# MCU_IO.net
KiCad netlist of a schematic drawn in Altium Designer
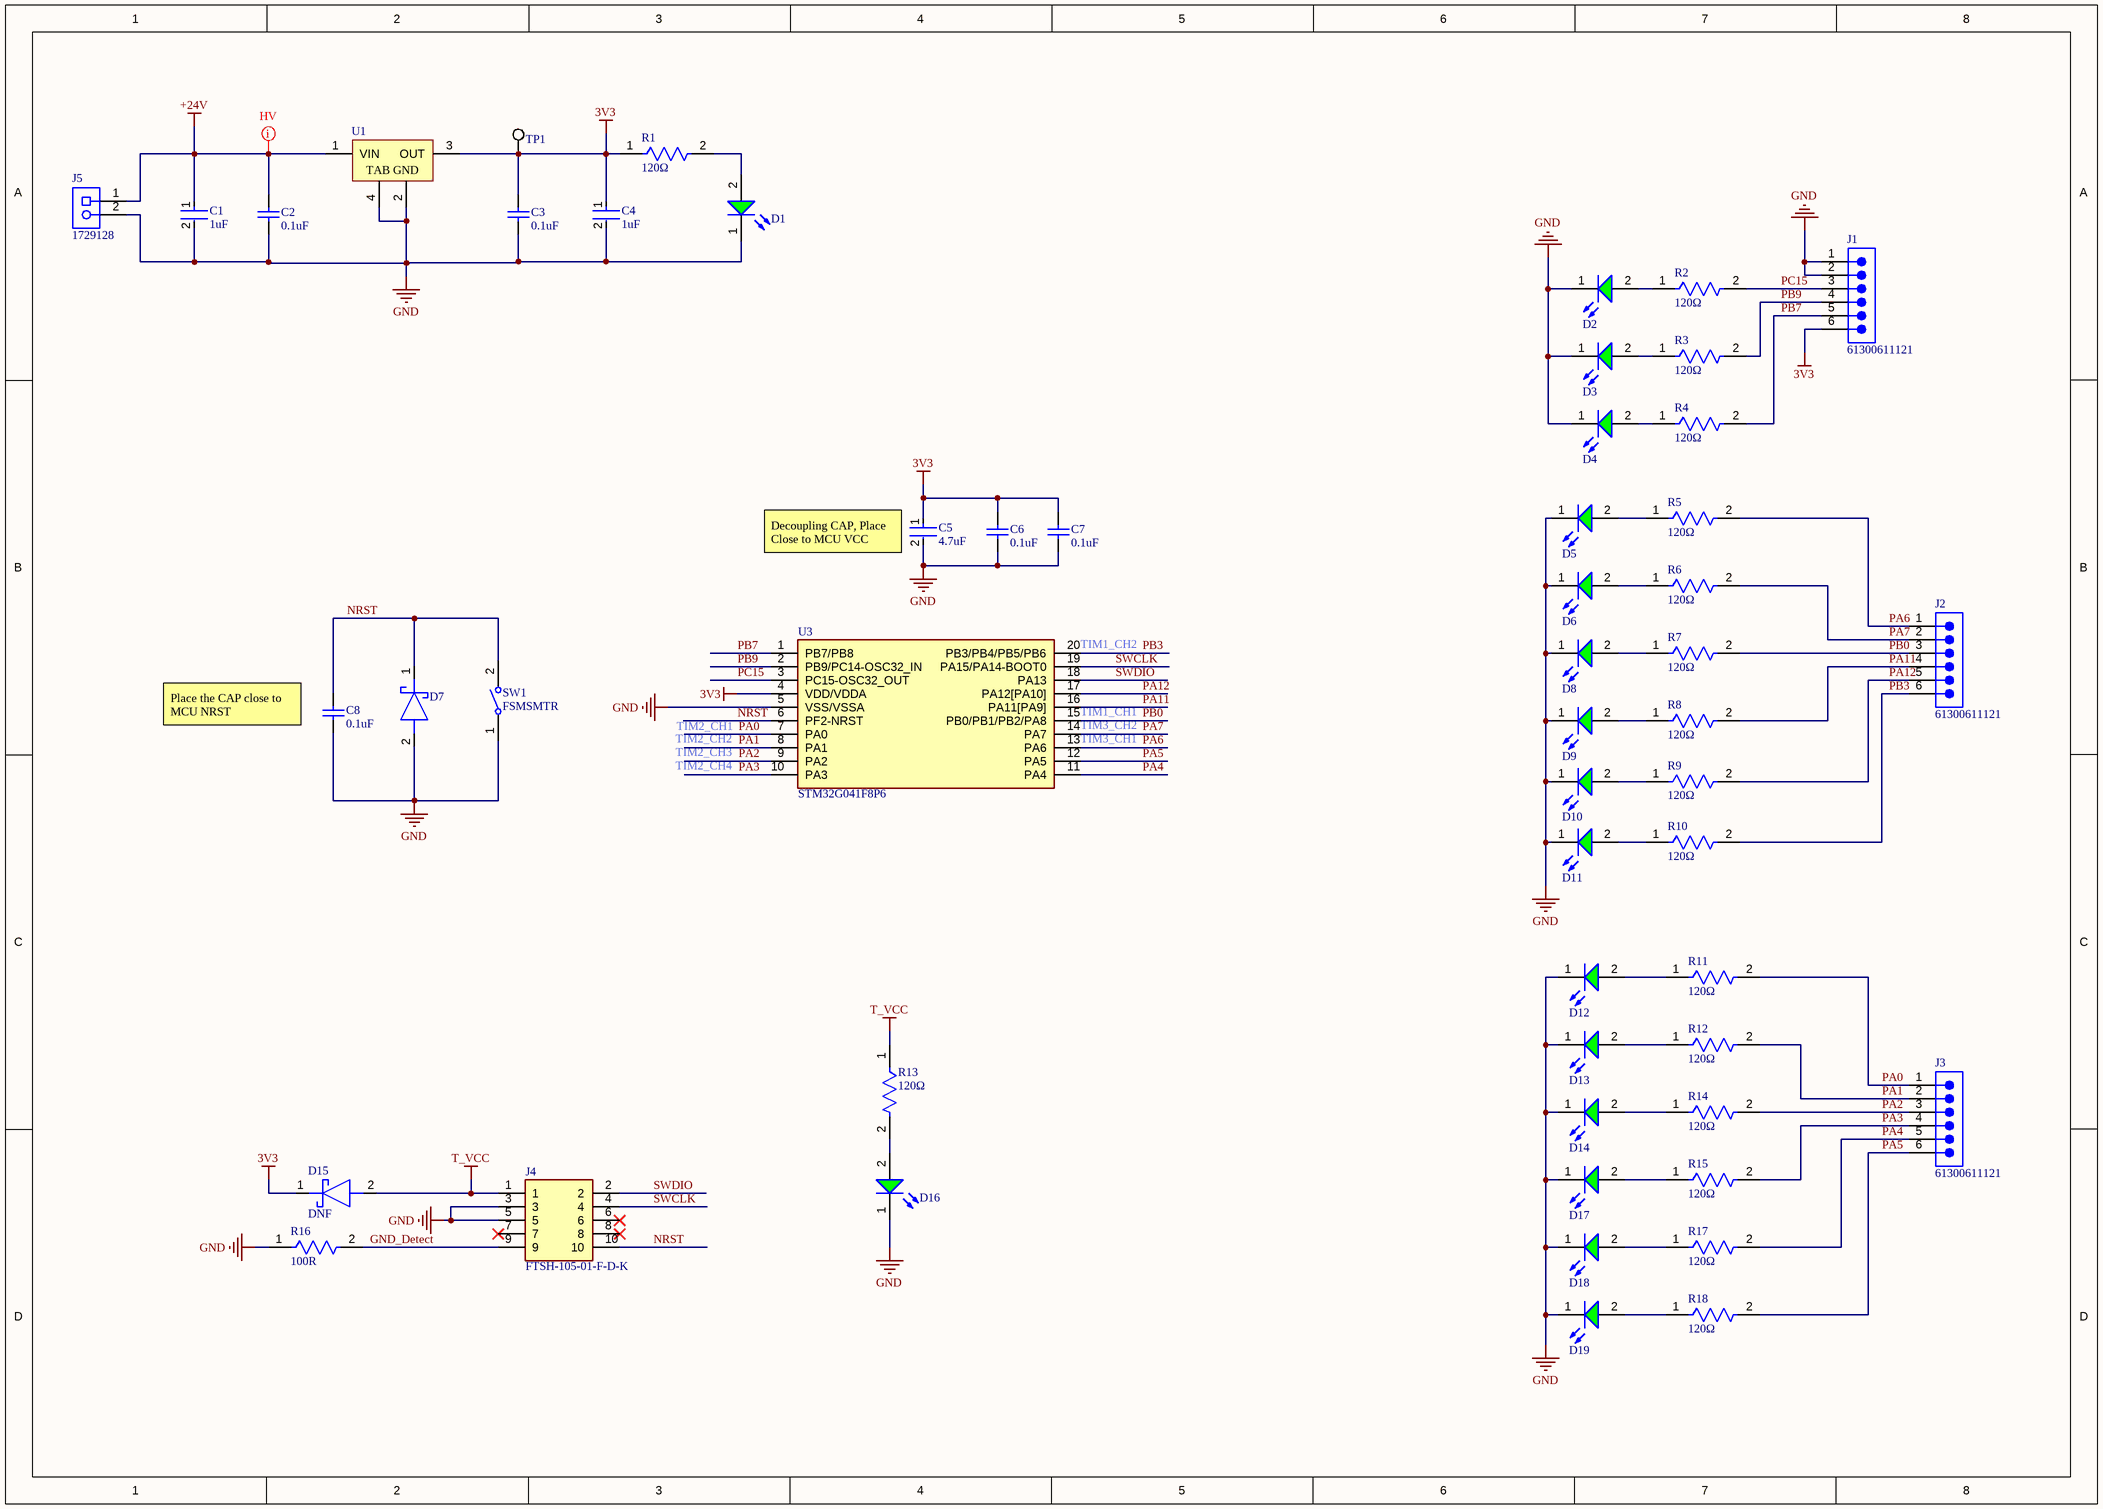
[diagram p0: MCU_IO.SchDoc]

(export (version "E")
  (design (tool "Eeschema 10.0.6"))
  (components
    (comp (ref "C1")
      (value "CC0805JKX7R9BB105")
      (footprint "FP-CC0805-0_2-1_45-MFG")
      (description "CAP CER 1UF 50V X7R 0805")
      (fields (field (name "CAPACITANCE") "1uF") (field (name "TOLERANCE") "5%"))
      (libsource (lib "Altium Content Vault") (part "02cd4be3c70576c341d710602a673aa"))
    )
    (comp (ref "C2")
      (value "0.1uF")
      (footprint "CAPC2013X94X50ML25T25")
      (description "CAP CER 0.1UF 100V X7R 0805")
      (fields
        (field (name "PART NUMBER") "LD051C104KAB2A")
        (field (name "MANUFACTURER") "AVX Interconnect / Elco")
      )
      (libsource (lib "Altium Content Vault") (part "CAP"))
    )
    (comp (ref "C3")
      (value "0.1uF")
      (footprint "CAPC2013X94X50ML25T25")
      (description "CAP CER 0.1UF 100V X7R 0805")
      (fields
        (field (name "PART NUMBER") "LD051C104KAB2A")
        (field (name "MANUFACTURER") "AVX Interconnect / Elco")
      )
      (libsource (lib "Altium Content Vault") (part "CAP"))
    )
    (comp (ref "C4")
      (value "CC0805JKX7R9BB105")
      (footprint "FP-CC0805-0_2-1_45-MFG")
      (description "CAP CER 1UF 50V X7R 0805")
      (fields (field (name "CAPACITANCE") "1uF") (field (name "TOLERANCE") "5%"))
      (libsource (lib "Altium Content Vault") (part "02cd4be3c70576c341d710602a673aa"))
    )
    (comp (ref "C5")
      (value "CGA4J3X7R1C475M125AE")
      (footprint "FP-CGA4J-IPC_B")
      (description "Cap Ceramic 4.7uF 16V X7R 20% Pad SMD 0805 +125°C Automotive T/R")
      (fields (field (name "TOLERANCE") "20%") (field (name "CAPACITANCE") "4.7uF"))
      (libsource (lib "Altium Content Vault") (part "b4654b650e69147ec39a6b967a45e02"))
    )
    (comp (ref "C6")
      (value "0.1uF")
      (footprint "CAPC2013X94X50ML25T25")
      (description "CAP CER 0.1UF 100V X7R 0805")
      (fields
        (field (name "PART NUMBER") "LD051C104KAB2A")
        (field (name "MANUFACTURER") "AVX Interconnect / Elco")
      )
      (libsource (lib "Altium Content Vault") (part "CAP"))
    )
    (comp (ref "C7")
      (value "0.1uF")
      (footprint "CAPC2013X94X50ML25T25")
      (description "CAP CER 0.1UF 100V X7R 0805")
      (fields
        (field (name "PART NUMBER") "LD051C104KAB2A")
        (field (name "MANUFACTURER") "AVX Interconnect / Elco")
      )
      (libsource (lib "Altium Content Vault") (part "CAP"))
    )
    (comp (ref "C8")
      (value "0.1uF")
      (footprint "CAPC2013X94X50ML25T25")
      (description "CAP CER 0.1UF 100V X7R 0805")
      (fields
        (field (name "PART NUMBER") "LD051C104KAB2A")
        (field (name "MANUFACTURER") "AVX Interconnect / Elco")
      )
      (libsource (lib "Altium Content Vault") (part "CAP"))
    )
    (comp (ref "D1")
      (value "150080GS75000")
      (footprint "WL-SMCW_0805_150080xx75000")
      (libsource (lib "Altium Content Vault") (part "LED_Green_2A-1K"))
    )
    (comp (ref "D2")
      (value "150080GS75000")
      (footprint "WL-SMCW_0805_150080xx75000")
      (libsource (lib "Altium Content Vault") (part "LED_Green_2A-1K"))
    )
    (comp (ref "D3")
      (value "150080GS75000")
      (footprint "WL-SMCW_0805_150080xx75000")
      (libsource (lib "Altium Content Vault") (part "LED_Green_2A-1K"))
    )
    (comp (ref "D4")
      (value "150080GS75000")
      (footprint "WL-SMCW_0805_150080xx75000")
      (libsource (lib "Altium Content Vault") (part "LED_Green_2A-1K"))
    )
    (comp (ref "D5")
      (value "150080GS75000")
      (footprint "WL-SMCW_0805_150080xx75000")
      (libsource (lib "Altium Content Vault") (part "LED_Green_2A-1K"))
    )
    (comp (ref "D6")
      (value "150080GS75000")
      (footprint "WL-SMCW_0805_150080xx75000")
      (libsource (lib "Altium Content Vault") (part "LED_Green_2A-1K"))
    )
    (comp (ref "D7")
      (value "SD0805S020S1R0")
      (footprint "SamacSys:SD0805S020S1R0")
      (description "Schottky Diode")
      (fields (field (name "MOUSER PART NUMBER") "581-SD0805S020S1R0"))
      (libsource (lib "*") (part "SD0805S020S1R0"))
    )
    (comp (ref "D8")
      (value "150080GS75000")
      (footprint "WL-SMCW_0805_150080xx75000")
      (libsource (lib "Altium Content Vault") (part "LED_Green_2A-1K"))
    )
    (comp (ref "D9")
      (value "150080GS75000")
      (footprint "WL-SMCW_0805_150080xx75000")
      (libsource (lib "Altium Content Vault") (part "LED_Green_2A-1K"))
    )
    (comp (ref "D10")
      (value "150080GS75000")
      (footprint "WL-SMCW_0805_150080xx75000")
      (libsource (lib "Altium Content Vault") (part "LED_Green_2A-1K"))
    )
    (comp (ref "D11")
      (value "150080GS75000")
      (footprint "WL-SMCW_0805_150080xx75000")
      (libsource (lib "Altium Content Vault") (part "LED_Green_2A-1K"))
    )
    (comp (ref "D12")
      (value "150080GS75000")
      (footprint "WL-SMCW_0805_150080xx75000")
      (libsource (lib "Altium Content Vault") (part "LED_Green_2A-1K"))
    )
    (comp (ref "D13")
      (value "150080GS75000")
      (footprint "WL-SMCW_0805_150080xx75000")
      (libsource (lib "Altium Content Vault") (part "LED_Green_2A-1K"))
    )
    (comp (ref "D14")
      (value "150080GS75000")
      (footprint "WL-SMCW_0805_150080xx75000")
      (libsource (lib "Altium Content Vault") (part "LED_Green_2A-1K"))
    )
    (comp (ref "D15")
      (value "DNF")
      (footprint "SamacSys:SD0805S020S1R0")
      (description "Schottky Diode")
      (fields
        (field (name "MANUFACTURER_PART_NUMBER") "SD0805S020S1R0")
        (field (name "MOUSER PART NUMBER") "581-SD0805S020S1R0")
      )
      (libsource (lib "*") (part "SD0805S020S1R0"))
    )
    (comp (ref "D16")
      (value "150080GS75000")
      (footprint "WL-SMCW_0805_150080xx75000")
      (libsource (lib "Altium Content Vault") (part "LED_Green_2A-1K"))
    )
    (comp (ref "D17")
      (value "150080GS75000")
      (footprint "WL-SMCW_0805_150080xx75000")
      (libsource (lib "Altium Content Vault") (part "LED_Green_2A-1K"))
    )
    (comp (ref "D18")
      (value "150080GS75000")
      (footprint "WL-SMCW_0805_150080xx75000")
      (libsource (lib "Altium Content Vault") (part "LED_Green_2A-1K"))
    )
    (comp (ref "D19")
      (value "150080GS75000")
      (footprint "WL-SMCW_0805_150080xx75000")
      (libsource (lib "Altium Content Vault") (part "LED_Green_2A-1K"))
    )
    (comp (ref "J1")
      (value "61300611121")
      (footprint "61300611121")
      (libsource (lib "Altium Content Vault") (part "Header_Male_1R_06P"))
    )
    (comp (ref "J2")
      (value "61300611121")
      (footprint "61300611121")
      (libsource (lib "Altium Content Vault") (part "Header_Male_1R_06P"))
    )
    (comp (ref "J3")
      (value "61300611121")
      (footprint "61300611121")
      (libsource (lib "Altium Content Vault") (part "Header_Male_1R_06P"))
    )
    (comp (ref "J4")
      (value "FTSH-105-01-F-D-K")
      (footprint "SamacSys:FTSH-105-XX-YYY-D-K")
      (description "Connector")
      (fields (field (name "MOUSER PART NUMBER") "200-FTSH10501FDK"))
      (libsource (lib "*") (part "FTSH-105-01-F-D-K"))
    )
    (comp (ref "J5")
      (value "1729128")
      (footprint "PHOE-1729128-2_V")
      (description "PCB Terminal Block, 13.5 A, 400 V, 2-Pin THD, RoHS, Bulk")
      (fields (field (name "MANUFACTURER") "Phoenix Contact"))
      (libsource (lib "Altium Content Vault") (part "CN-2P-F-R2"))
    )
    (comp (ref "R1")
      (value "CRGP0805F120R")
      (footprint "FP-CRGP0805-IPC_C")
      (description "CRGP0805 120Ω 0.33W ±100ppm/°C 1% 150V")
      (fields
        (field (name "RESISTANCE") "120Ω")
        (field (name "OCTOPART") "https://octopart.com/crgp0805f120r-te+connectivity-91018785")
        (field (name "MANUFACTURER") "TE")
      )
      (libsource (lib "Altium Content Vault") (part "1029c3af85768c4190bb7ad29bc67b5"))
    )
    (comp (ref "R2")
      (value "CRGP0805F120R")
      (footprint "FP-CRGP0805-IPC_C")
      (description "CRGP0805 120Ω 0.33W ±100ppm/°C 1% 150V")
      (fields
        (field (name "RESISTANCE") "120Ω")
        (field (name "OCTOPART") "https://octopart.com/crgp0805f120r-te+connectivity-91018785")
        (field (name "MANUFACTURER") "TE")
      )
      (libsource (lib "Altium Content Vault") (part "1029c3af85768c4190bb7ad29bc67b5"))
    )
    (comp (ref "R3")
      (value "CRGP0805F120R")
      (footprint "FP-CRGP0805-IPC_C")
      (description "CRGP0805 120Ω 0.33W ±100ppm/°C 1% 150V")
      (fields
        (field (name "RESISTANCE") "120Ω")
        (field (name "OCTOPART") "https://octopart.com/crgp0805f120r-te+connectivity-91018785")
        (field (name "MANUFACTURER") "TE")
      )
      (libsource (lib "Altium Content Vault") (part "1029c3af85768c4190bb7ad29bc67b5"))
    )
    (comp (ref "R4")
      (value "CRGP0805F120R")
      (footprint "FP-CRGP0805-IPC_C")
      (description "CRGP0805 120Ω 0.33W ±100ppm/°C 1% 150V")
      (fields
        (field (name "RESISTANCE") "120Ω")
        (field (name "OCTOPART") "https://octopart.com/crgp0805f120r-te+connectivity-91018785")
        (field (name "MANUFACTURER") "TE")
      )
      (libsource (lib "Altium Content Vault") (part "1029c3af85768c4190bb7ad29bc67b5"))
    )
    (comp (ref "R5")
      (value "CRGP0805F120R")
      (footprint "FP-CRGP0805-IPC_C")
      (description "CRGP0805 120Ω 0.33W ±100ppm/°C 1% 150V")
      (fields
        (field (name "RESISTANCE") "120Ω")
        (field (name "OCTOPART") "https://octopart.com/crgp0805f120r-te+connectivity-91018785")
        (field (name "MANUFACTURER") "TE")
      )
      (libsource (lib "Altium Content Vault") (part "1029c3af85768c4190bb7ad29bc67b5"))
    )
    (comp (ref "R6")
      (value "CRGP0805F120R")
      (footprint "FP-CRGP0805-IPC_C")
      (description "CRGP0805 120Ω 0.33W ±100ppm/°C 1% 150V")
      (fields
        (field (name "RESISTANCE") "120Ω")
        (field (name "OCTOPART") "https://octopart.com/crgp0805f120r-te+connectivity-91018785")
        (field (name "MANUFACTURER") "TE")
      )
      (libsource (lib "Altium Content Vault") (part "1029c3af85768c4190bb7ad29bc67b5"))
    )
    (comp (ref "R7")
      (value "CRGP0805F120R")
      (footprint "FP-CRGP0805-IPC_C")
      (description "CRGP0805 120Ω 0.33W ±100ppm/°C 1% 150V")
      (fields
        (field (name "RESISTANCE") "120Ω")
        (field (name "OCTOPART") "https://octopart.com/crgp0805f120r-te+connectivity-91018785")
        (field (name "MANUFACTURER") "TE")
      )
      (libsource (lib "Altium Content Vault") (part "1029c3af85768c4190bb7ad29bc67b5"))
    )
    (comp (ref "R8")
      (value "CRGP0805F120R")
      (footprint "FP-CRGP0805-IPC_C")
      (description "CRGP0805 120Ω 0.33W ±100ppm/°C 1% 150V")
      (fields
        (field (name "RESISTANCE") "120Ω")
        (field (name "OCTOPART") "https://octopart.com/crgp0805f120r-te+connectivity-91018785")
        (field (name "MANUFACTURER") "TE")
      )
      (libsource (lib "Altium Content Vault") (part "1029c3af85768c4190bb7ad29bc67b5"))
    )
    (comp (ref "R9")
      (value "CRGP0805F120R")
      (footprint "FP-CRGP0805-IPC_C")
      (description "CRGP0805 120Ω 0.33W ±100ppm/°C 1% 150V")
      (fields
        (field (name "RESISTANCE") "120Ω")
        (field (name "OCTOPART") "https://octopart.com/crgp0805f120r-te+connectivity-91018785")
        (field (name "MANUFACTURER") "TE")
      )
      (libsource (lib "Altium Content Vault") (part "1029c3af85768c4190bb7ad29bc67b5"))
    )
    (comp (ref "R10")
      (value "CRGP0805F120R")
      (footprint "FP-CRGP0805-IPC_C")
      (description "CRGP0805 120Ω 0.33W ±100ppm/°C 1% 150V")
      (fields
        (field (name "RESISTANCE") "120Ω")
        (field (name "OCTOPART") "https://octopart.com/crgp0805f120r-te+connectivity-91018785")
        (field (name "MANUFACTURER") "TE")
      )
      (libsource (lib "Altium Content Vault") (part "1029c3af85768c4190bb7ad29bc67b5"))
    )
    (comp (ref "R11")
      (value "CRGP0805F120R")
      (footprint "FP-CRGP0805-IPC_C")
      (description "CRGP0805 120Ω 0.33W ±100ppm/°C 1% 150V")
      (fields
        (field (name "RESISTANCE") "120Ω")
        (field (name "OCTOPART") "https://octopart.com/crgp0805f120r-te+connectivity-91018785")
        (field (name "MANUFACTURER") "TE")
      )
      (libsource (lib "Altium Content Vault") (part "1029c3af85768c4190bb7ad29bc67b5"))
    )
    (comp (ref "R12")
      (value "CRGP0805F120R")
      (footprint "FP-CRGP0805-IPC_C")
      (description "CRGP0805 120Ω 0.33W ±100ppm/°C 1% 150V")
      (fields
        (field (name "RESISTANCE") "120Ω")
        (field (name "OCTOPART") "https://octopart.com/crgp0805f120r-te+connectivity-91018785")
        (field (name "MANUFACTURER") "TE")
      )
      (libsource (lib "Altium Content Vault") (part "1029c3af85768c4190bb7ad29bc67b5"))
    )
    (comp (ref "R13")
      (value "CRGP0805F120R")
      (footprint "FP-CRGP0805-IPC_C")
      (description "CRGP0805 120Ω 0.33W ±100ppm/°C 1% 150V")
      (fields
        (field (name "RESISTANCE") "120Ω")
        (field (name "OCTOPART") "https://octopart.com/crgp0805f120r-te+connectivity-91018785")
        (field (name "MANUFACTURER") "TE")
      )
      (libsource (lib "Altium Content Vault") (part "1029c3af85768c4190bb7ad29bc67b5"))
    )
    (comp (ref "R14")
      (value "CRGP0805F120R")
      (footprint "FP-CRGP0805-IPC_C")
      (description "CRGP0805 120Ω 0.33W ±100ppm/°C 1% 150V")
      (fields
        (field (name "RESISTANCE") "120Ω")
        (field (name "OCTOPART") "https://octopart.com/crgp0805f120r-te+connectivity-91018785")
        (field (name "MANUFACTURER") "TE")
      )
      (libsource (lib "Altium Content Vault") (part "1029c3af85768c4190bb7ad29bc67b5"))
    )
    (comp (ref "R15")
      (value "CRGP0805F120R")
      (footprint "FP-CRGP0805-IPC_C")
      (description "CRGP0805 120Ω 0.33W ±100ppm/°C 1% 150V")
      (fields
        (field (name "RESISTANCE") "120Ω")
        (field (name "OCTOPART") "https://octopart.com/crgp0805f120r-te+connectivity-91018785")
        (field (name "MANUFACTURER") "TE")
      )
      (libsource (lib "Altium Content Vault") (part "1029c3af85768c4190bb7ad29bc67b5"))
    )
    (comp (ref "R16")
      (value "CRCW0805100RJNEAHP")
      (footprint "FP-CRCW0805-HPe3-IPC_C")
      (description "RES Thick Film, 100Ω, 5%, 0.5W, 200ppm/°C, 0805")
      (fields (field (name "RESISTANCE") "100R") (field (name "TOLERANCE") "5%"))
      (libsource (lib "Altium Content Vault") (part "1029c3af85768c4190bb7ad29bc67b5"))
    )
    (comp (ref "R17")
      (value "CRGP0805F120R")
      (footprint "FP-CRGP0805-IPC_C")
      (description "CRGP0805 120Ω 0.33W ±100ppm/°C 1% 150V")
      (fields
        (field (name "RESISTANCE") "120Ω")
        (field (name "OCTOPART") "https://octopart.com/crgp0805f120r-te+connectivity-91018785")
        (field (name "MANUFACTURER") "TE")
      )
      (libsource (lib "Altium Content Vault") (part "1029c3af85768c4190bb7ad29bc67b5"))
    )
    (comp (ref "R18")
      (value "CRGP0805F120R")
      (footprint "FP-CRGP0805-IPC_C")
      (description "CRGP0805 120Ω 0.33W ±100ppm/°C 1% 150V")
      (fields
        (field (name "RESISTANCE") "120Ω")
        (field (name "OCTOPART") "https://octopart.com/crgp0805f120r-te+connectivity-91018785")
        (field (name "MANUFACTURER") "TE")
      )
      (libsource (lib "Altium Content Vault") (part "1029c3af85768c4190bb7ad29bc67b5"))
    )
    (comp (ref "SW1")
      (value "FSMSMTR")
      (footprint "TECO-FSMSMTR_V")
      (description "FSMSM Push Button Switch, 50 mA, -35 to 85 degC, 2-Pin SMD, RoHS, Tape and Reel")
      (fields (field (name "MANUFACTURER") "TE Connectivity"))
      (libsource (lib "Altium Content Vault") (part "SW-SPST-2_C"))
    )
    (comp (ref "TP1")
      (value "5019")
      (footprint "KSTN-5019_V")
      (description "Test Point, 1 Position SMD, RoHS, Tape and Reel")
      (libsource (lib "Altium Content Vault") (part "TESTPOINT_WHITE"))
    )
    (comp (ref "U1")
      (value "LT1129IST-3.3#TRPBF")
      (footprint "LT-ST-3-SOT-223_L")
      (fields (field (name "MANUFACTURER") "Linear Technology"))
      (libsource (lib "Altium Content Vault") (part "LT-LT112X-ST-3"))
    )
    (comp (ref "U3")
      (value "STM32G041F8P6")
      (footprint "SamacSys:CLT34BT6")
      (description "Integrated Circuit")
      (fields (field (name "MOUSER PART NUMBER") "511-STM32G041F8P6"))
      (libsource (lib "*") (part "STM32G041F8P6"))
    )
  )
  (nets
    (net (code "1") (name "+24V") (class "Default")
      (node (ref "C1") (pin "1") (pinfunction "1_1") (pintype "passive"))
      (node (ref "C2") (pin "2") (pinfunction "2_2") (pintype "passive"))
      (node (ref "J5") (pin "1") (pinfunction "1_1") (pintype "passive"))
      (node (ref "U1") (pin "1") (pinfunction "VIN_1") (pintype "power_in"))
    )
    (net (code "2") (name "/GND_Detect") (class "Default")
      (node (ref "J4") (pin "9") (pinfunction "9_9") (pintype "passive"))
      (node (ref "R16") (pin "2") (pinfunction "2_2") (pintype "passive"))
    )
    (net (code "3") (name "/NRST") (class "Default")
      (node (ref "C8") (pin "2") (pinfunction "2_2") (pintype "passive"))
      (node (ref "D7") (pin "1") (pinfunction "K_1") (pintype "passive"))
      (node (ref "J4") (pin "10") (pinfunction "10_10") (pintype "passive"))
      (node (ref "SW1") (pin "2") (pinfunction "2_2") (pintype "passive"))
      (node (ref "U3") (pin "6") (pinfunction "PF2-NRST_6") (pintype "passive"))
    )
    (net (code "4") (name "/PA0") (class "Default")
      (node (ref "J3") (pin "1") (pinfunction "1_1") (pintype "passive"))
      (node (ref "R11") (pin "2") (pinfunction "2_2") (pintype "passive"))
      (node (ref "U3") (pin "7") (pinfunction "PA0_7") (pintype "passive"))
    )
    (net (code "5") (name "/PA1") (class "Default")
      (node (ref "J3") (pin "2") (pinfunction "2_2") (pintype "passive"))
      (node (ref "R12") (pin "2") (pinfunction "2_2") (pintype "passive"))
      (node (ref "U3") (pin "8") (pinfunction "PA1_8") (pintype "passive"))
    )
    (net (code "6") (name "/PA2") (class "Default")
      (node (ref "J3") (pin "3") (pinfunction "3_3") (pintype "passive"))
      (node (ref "R14") (pin "2") (pinfunction "2_2") (pintype "passive"))
      (node (ref "U3") (pin "9") (pinfunction "PA2_9") (pintype "passive"))
    )
    (net (code "7") (name "/PA3") (class "Default")
      (node (ref "J3") (pin "4") (pinfunction "4_4") (pintype "passive"))
      (node (ref "R15") (pin "2") (pinfunction "2_2") (pintype "passive"))
      (node (ref "U3") (pin "10") (pinfunction "PA3_10") (pintype "passive"))
    )
    (net (code "8") (name "/PA4") (class "Default")
      (node (ref "J3") (pin "5") (pinfunction "5_5") (pintype "passive"))
      (node (ref "R17") (pin "2") (pinfunction "2_2") (pintype "passive"))
      (node (ref "U3") (pin "11") (pinfunction "PA4_11") (pintype "passive"))
    )
    (net (code "9") (name "/PA5") (class "Default")
      (node (ref "J3") (pin "6") (pinfunction "6_6") (pintype "passive"))
      (node (ref "R18") (pin "2") (pinfunction "2_2") (pintype "passive"))
      (node (ref "U3") (pin "12") (pinfunction "PA5_12") (pintype "passive"))
    )
    (net (code "10") (name "/PA6") (class "Default")
      (node (ref "J2") (pin "1") (pinfunction "1_1") (pintype "passive"))
      (node (ref "R5") (pin "2") (pinfunction "2_2") (pintype "passive"))
      (node (ref "U3") (pin "13") (pinfunction "PA6_13") (pintype "passive"))
    )
    (net (code "11") (name "/PA7") (class "Default")
      (node (ref "J2") (pin "2") (pinfunction "2_2") (pintype "passive"))
      (node (ref "R6") (pin "2") (pinfunction "2_2") (pintype "passive"))
      (node (ref "U3") (pin "14") (pinfunction "PA7_14") (pintype "passive"))
    )
    (net (code "12") (name "/PA11") (class "Default")
      (node (ref "J2") (pin "4") (pinfunction "4_4") (pintype "passive"))
      (node (ref "R8") (pin "2") (pinfunction "2_2") (pintype "passive"))
      (node (ref "U3") (pin "16") (pinfunction "PA11[PA9]_16") (pintype "passive"))
    )
    (net (code "13") (name "/PA12") (class "Default")
      (node (ref "J2") (pin "5") (pinfunction "5_5") (pintype "passive"))
      (node (ref "R9") (pin "2") (pinfunction "2_2") (pintype "passive"))
      (node (ref "U3") (pin "17") (pinfunction "PA12[PA10]_17") (pintype "passive"))
    )
    (net (code "14") (name "/PB0") (class "Default")
      (node (ref "J2") (pin "3") (pinfunction "3_3") (pintype "passive"))
      (node (ref "R7") (pin "2") (pinfunction "2_2") (pintype "passive"))
      (node (ref "U3") (pin "15") (pinfunction "PB0/PB1/PB2/PA8_15") (pintype "passive"))
    )
    (net (code "15") (name "/PB3") (class "Default")
      (node (ref "J2") (pin "6") (pinfunction "6_6") (pintype "passive"))
      (node (ref "R10") (pin "2") (pinfunction "2_2") (pintype "passive"))
      (node (ref "U3") (pin "20") (pinfunction "PB3/PB4/PB5/PB6_20") (pintype "passive"))
    )
    (net (code "16") (name "/PB7") (class "Default")
      (node (ref "J1") (pin "5") (pinfunction "5_5") (pintype "passive"))
      (node (ref "R4") (pin "2") (pinfunction "2_2") (pintype "passive"))
      (node (ref "U3") (pin "1") (pinfunction "PB7/PB8_1") (pintype "passive"))
    )
    (net (code "17") (name "/PB9") (class "Default")
      (node (ref "J1") (pin "4") (pinfunction "4_4") (pintype "passive"))
      (node (ref "R3") (pin "2") (pinfunction "2_2") (pintype "passive"))
      (node (ref "U3") (pin "2") (pinfunction "PB9/PC14-OSC32_IN_2") (pintype "passive"))
    )
    (net (code "18") (name "/PC15") (class "Default")
      (node (ref "J1") (pin "3") (pinfunction "3_3") (pintype "passive"))
      (node (ref "R2") (pin "2") (pinfunction "2_2") (pintype "passive"))
      (node (ref "U3") (pin "3") (pinfunction "PC15-OSC32_OUT_3") (pintype "passive"))
    )
    (net (code "19") (name "/SWCLK") (class "Default")
      (node (ref "J4") (pin "4") (pinfunction "4_4") (pintype "passive"))
      (node (ref "U3") (pin "19") (pinfunction "PA15/PA14-BOOT0_19") (pintype "passive"))
    )
    (net (code "20") (name "/SWDIO") (class "Default")
      (node (ref "J4") (pin "2") (pinfunction "2_2") (pintype "passive"))
      (node (ref "U3") (pin "18") (pinfunction "PA13_18") (pintype "passive"))
    )
    (net (code "21") (name "3V3") (class "Default")
      (node (ref "C3") (pin "2") (pinfunction "2_2") (pintype "passive"))
      (node (ref "C4") (pin "1") (pinfunction "1_1") (pintype "passive"))
      (node (ref "C5") (pin "1") (pinfunction "1_1") (pintype "passive"))
      (node (ref "C6") (pin "2") (pinfunction "2_2") (pintype "passive"))
      (node (ref "C7") (pin "2") (pinfunction "2_2") (pintype "passive"))
      (node (ref "D15") (pin "1") (pinfunction "K_1") (pintype "passive"))
      (node (ref "J1") (pin "6") (pinfunction "6_6") (pintype "passive"))
      (node (ref "R1") (pin "1") (pinfunction "1_1") (pintype "passive"))
      (node (ref "TP1") (pin "1") (pinfunction "1_1") (pintype "passive"))
      (node (ref "U1") (pin "3") (pinfunction "OUT_3") (pintype "power_in"))
      (node (ref "U3") (pin "4") (pinfunction "VDD/VDDA_4") (pintype "passive"))
    )
    (net (code "22") (name "GND") (class "Default")
      (node (ref "C1") (pin "2") (pinfunction "2_2") (pintype "passive"))
      (node (ref "C2") (pin "1") (pinfunction "1_1") (pintype "passive"))
      (node (ref "C3") (pin "1") (pinfunction "1_1") (pintype "passive"))
      (node (ref "C4") (pin "2") (pinfunction "2_2") (pintype "passive"))
      (node (ref "C5") (pin "2") (pinfunction "2_2") (pintype "passive"))
      (node (ref "C6") (pin "1") (pinfunction "1_1") (pintype "passive"))
      (node (ref "C7") (pin "1") (pinfunction "1_1") (pintype "passive"))
      (node (ref "C8") (pin "1") (pinfunction "1_1") (pintype "passive"))
      (node (ref "D1") (pin "1") (pinfunction "K_1") (pintype "passive"))
      (node (ref "D10") (pin "1") (pinfunction "K_1") (pintype "passive"))
      (node (ref "D11") (pin "1") (pinfunction "K_1") (pintype "passive"))
      (node (ref "D12") (pin "1") (pinfunction "K_1") (pintype "passive"))
      (node (ref "D13") (pin "1") (pinfunction "K_1") (pintype "passive"))
      (node (ref "D14") (pin "1") (pinfunction "K_1") (pintype "passive"))
      (node (ref "D16") (pin "1") (pinfunction "K_1") (pintype "passive"))
      (node (ref "D17") (pin "1") (pinfunction "K_1") (pintype "passive"))
      (node (ref "D18") (pin "1") (pinfunction "K_1") (pintype "passive"))
      (node (ref "D19") (pin "1") (pinfunction "K_1") (pintype "passive"))
      (node (ref "D2") (pin "1") (pinfunction "K_1") (pintype "passive"))
      (node (ref "D3") (pin "1") (pinfunction "K_1") (pintype "passive"))
      (node (ref "D4") (pin "1") (pinfunction "K_1") (pintype "passive"))
      (node (ref "D5") (pin "1") (pinfunction "K_1") (pintype "passive"))
      (node (ref "D6") (pin "1") (pinfunction "K_1") (pintype "passive"))
      (node (ref "D7") (pin "2") (pinfunction "A_2") (pintype "passive"))
      (node (ref "D8") (pin "1") (pinfunction "K_1") (pintype "passive"))
      (node (ref "D9") (pin "1") (pinfunction "K_1") (pintype "passive"))
      (node (ref "J1") (pin "1") (pinfunction "1_1") (pintype "passive"))
      (node (ref "J1") (pin "2") (pinfunction "2_2") (pintype "passive"))
      (node (ref "J4") (pin "3") (pinfunction "3_3") (pintype "passive"))
      (node (ref "J4") (pin "5") (pinfunction "5_5") (pintype "passive"))
      (node (ref "J5") (pin "2") (pinfunction "2_2") (pintype "passive"))
      (node (ref "R16") (pin "1") (pinfunction "1_1") (pintype "passive"))
      (node (ref "SW1") (pin "1") (pinfunction "1_1") (pintype "passive"))
      (node (ref "U1") (pin "2") (pinfunction "GND_2") (pintype "power_in"))
      (node (ref "U1") (pin "4") (pinfunction "TAB_4") (pintype "power_in"))
      (node (ref "U3") (pin "5") (pinfunction "VSS/VSSA_5") (pintype "passive"))
    )
    (net (code "23") (name "Net-(D1-A)") (class "Default")
      (node (ref "D1") (pin "2") (pinfunction "A_2") (pintype "passive"))
      (node (ref "R1") (pin "2") (pinfunction "2_2") (pintype "passive"))
    )
    (net (code "24") (name "Net-(D2-A)") (class "Default")
      (node (ref "D2") (pin "2") (pinfunction "A_2") (pintype "passive"))
      (node (ref "R2") (pin "1") (pinfunction "1_1") (pintype "passive"))
    )
    (net (code "25") (name "Net-(D3-A)") (class "Default")
      (node (ref "D3") (pin "2") (pinfunction "A_2") (pintype "passive"))
      (node (ref "R3") (pin "1") (pinfunction "1_1") (pintype "passive"))
    )
    (net (code "26") (name "Net-(D4-A)") (class "Default")
      (node (ref "D4") (pin "2") (pinfunction "A_2") (pintype "passive"))
      (node (ref "R4") (pin "1") (pinfunction "1_1") (pintype "passive"))
    )
    (net (code "27") (name "Net-(D5-A)") (class "Default")
      (node (ref "D5") (pin "2") (pinfunction "A_2") (pintype "passive"))
      (node (ref "R5") (pin "1") (pinfunction "1_1") (pintype "passive"))
    )
    (net (code "28") (name "Net-(D6-A)") (class "Default")
      (node (ref "D6") (pin "2") (pinfunction "A_2") (pintype "passive"))
      (node (ref "R6") (pin "1") (pinfunction "1_1") (pintype "passive"))
    )
    (net (code "29") (name "Net-(D8-A)") (class "Default")
      (node (ref "D8") (pin "2") (pinfunction "A_2") (pintype "passive"))
      (node (ref "R7") (pin "1") (pinfunction "1_1") (pintype "passive"))
    )
    (net (code "30") (name "Net-(D9-A)") (class "Default")
      (node (ref "D9") (pin "2") (pinfunction "A_2") (pintype "passive"))
      (node (ref "R8") (pin "1") (pinfunction "1_1") (pintype "passive"))
    )
    (net (code "31") (name "Net-(D10-A)") (class "Default")
      (node (ref "D10") (pin "2") (pinfunction "A_2") (pintype "passive"))
      (node (ref "R9") (pin "1") (pinfunction "1_1") (pintype "passive"))
    )
    (net (code "32") (name "Net-(D11-A)") (class "Default")
      (node (ref "D11") (pin "2") (pinfunction "A_2") (pintype "passive"))
      (node (ref "R10") (pin "1") (pinfunction "1_1") (pintype "passive"))
    )
    (net (code "33") (name "Net-(D12-A)") (class "Default")
      (node (ref "D12") (pin "2") (pinfunction "A_2") (pintype "passive"))
      (node (ref "R11") (pin "1") (pinfunction "1_1") (pintype "passive"))
    )
    (net (code "34") (name "Net-(D13-A)") (class "Default")
      (node (ref "D13") (pin "2") (pinfunction "A_2") (pintype "passive"))
      (node (ref "R12") (pin "1") (pinfunction "1_1") (pintype "passive"))
    )
    (net (code "35") (name "Net-(D14-A)") (class "Default")
      (node (ref "D14") (pin "2") (pinfunction "A_2") (pintype "passive"))
      (node (ref "R14") (pin "1") (pinfunction "1_1") (pintype "passive"))
    )
    (net (code "36") (name "Net-(D16-A)") (class "Default")
      (node (ref "D16") (pin "2") (pinfunction "A_2") (pintype "passive"))
      (node (ref "R13") (pin "2") (pinfunction "2_2") (pintype "passive"))
    )
    (net (code "37") (name "Net-(D17-A)") (class "Default")
      (node (ref "D17") (pin "2") (pinfunction "A_2") (pintype "passive"))
      (node (ref "R15") (pin "1") (pinfunction "1_1") (pintype "passive"))
    )
    (net (code "38") (name "Net-(D18-A)") (class "Default")
      (node (ref "D18") (pin "2") (pinfunction "A_2") (pintype "passive"))
      (node (ref "R17") (pin "1") (pinfunction "1_1") (pintype "passive"))
    )
    (net (code "39") (name "Net-(D19-A)") (class "Default")
      (node (ref "D19") (pin "2") (pinfunction "A_2") (pintype "passive"))
      (node (ref "R18") (pin "1") (pinfunction "1_1") (pintype "passive"))
    )
    (net (code "40") (name "T_VCC") (class "Default")
      (node (ref "D15") (pin "2") (pinfunction "A_2") (pintype "passive"))
      (node (ref "J4") (pin "1") (pinfunction "1_1") (pintype "passive"))
      (node (ref "R13") (pin "1") (pinfunction "1_1") (pintype "passive"))
    )
    (net (code "41") (name "unconnected-(J4-Pad6)") (class "Default")
      (node (ref "J4") (pin "6") (pinfunction "6_6") (pintype "passive+no_connect"))
    )
    (net (code "42") (name "unconnected-(J4-Pad7)") (class "Default")
      (node (ref "J4") (pin "7") (pinfunction "7_7") (pintype "passive+no_connect"))
    )
    (net (code "43") (name "unconnected-(J4-Pad8)") (class "Default")
      (node (ref "J4") (pin "8") (pinfunction "8_8") (pintype "passive+no_connect"))
    )
  )
)
